# limit_switches.net
KiCad netlist of a schematic drawn in Altium Designer
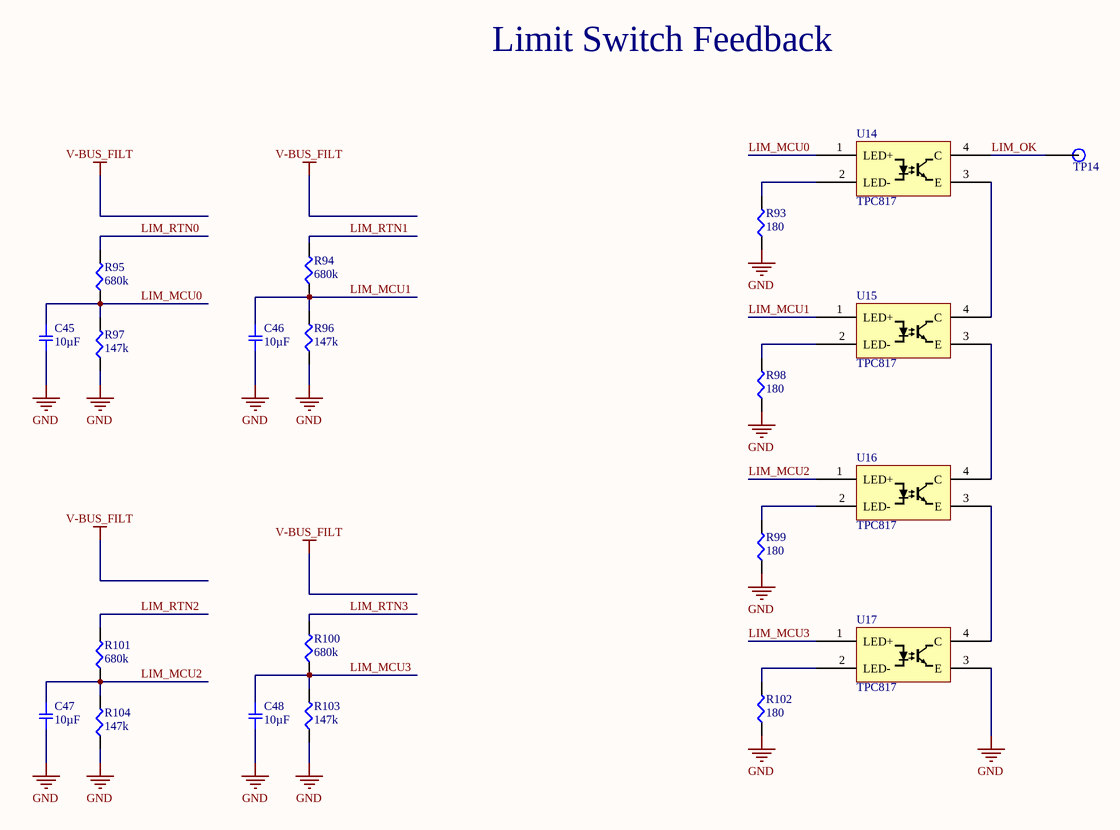
[diagram p0: limit_switches.SchDoc]

(export (version "E")
  (design (tool "Eeschema 10.0.6"))
  (components
    (comp (ref "C45")
      (value "10µF")
      (footprint "SMD-0805C")
      (description "CAP CER 10UF 25V X6S 0805")
      (fields
        (field (name "DIGI-KEY PART NUMBER") "490-10502-1-ND")
        (field (name "PART NUMBER") "GRM21BC81E106KE51L")
      )
      (libsource (lib "capacitor") (part "GRM21BC81E106KE51L"))
    )
    (comp (ref "C46")
      (value "10µF")
      (footprint "SMD-0805C")
      (description "CAP CER 10UF 25V X6S 0805")
      (fields
        (field (name "DIGI-KEY PART NUMBER") "490-10502-1-ND")
        (field (name "PART NUMBER") "GRM21BC81E106KE51L")
      )
      (libsource (lib "capacitor") (part "GRM21BC81E106KE51L"))
    )
    (comp (ref "C47")
      (value "10µF")
      (footprint "SMD-0805C")
      (description "CAP CER 10UF 25V X6S 0805")
      (fields
        (field (name "DIGI-KEY PART NUMBER") "490-10502-1-ND")
        (field (name "PART NUMBER") "GRM21BC81E106KE51L")
      )
      (libsource (lib "capacitor") (part "GRM21BC81E106KE51L"))
    )
    (comp (ref "C48")
      (value "10µF")
      (footprint "SMD-0805C")
      (description "CAP CER 10UF 25V X6S 0805")
      (fields
        (field (name "DIGI-KEY PART NUMBER") "490-10502-1-ND")
        (field (name "PART NUMBER") "GRM21BC81E106KE51L")
      )
      (libsource (lib "capacitor") (part "GRM21BC81E106KE51L"))
    )
    (comp (ref "R93")
      (value "180")
      (footprint "SMD-0805-RES")
      (description "RES SMD 180 OHM 1% 1/8W 0805")
      (fields (field (name "PART NUMBER") "ERJ-6ENF1800V") (field (name "DIGI-KEY PART NUMBER") "P180CCT-ND"))
      (libsource (lib "resistors") (part "ERJ-6ENF1800V"))
    )
    (comp (ref "R94")
      (value "680k")
      (footprint "SMD-0805-RES")
      (description "RES SMD 680K OHM 1% 1/8W 0805")
      (fields
        (field (name "PART NUMBER") "ERJ-6ENF6803V")
        (field (name "DIGI-KEY PART NUMBER") "P680KCCT-ND")
      )
      (libsource (lib "resistors") (part "ERJ-6ENF6803V"))
    )
    (comp (ref "R95")
      (value "680k")
      (footprint "SMD-0805-RES")
      (description "RES SMD 680K OHM 1% 1/8W 0805")
      (fields
        (field (name "PART NUMBER") "ERJ-6ENF6803V")
        (field (name "DIGI-KEY PART NUMBER") "P680KCCT-ND")
      )
      (libsource (lib "resistors") (part "ERJ-6ENF6803V"))
    )
    (comp (ref "R96")
      (value "147k")
      (footprint "SMD-0805-RES")
      (description "RES SMD 147K OHM 1% 1/8W 0805")
      (fields
        (field (name "PART NUMBER") "ERJ-6ENF1473V")
        (field (name "DIGI-KEY PART NUMBER") "P147KCCT-ND")
      )
      (libsource (lib "resistors") (part "ERJ-6ENF1473V"))
    )
    (comp (ref "R97")
      (value "147k")
      (footprint "SMD-0805-RES")
      (description "RES SMD 147K OHM 1% 1/8W 0805")
      (fields
        (field (name "PART NUMBER") "ERJ-6ENF1473V")
        (field (name "DIGI-KEY PART NUMBER") "P147KCCT-ND")
      )
      (libsource (lib "resistors") (part "ERJ-6ENF1473V"))
    )
    (comp (ref "R98")
      (value "180")
      (footprint "SMD-0805-RES")
      (description "RES SMD 180 OHM 1% 1/8W 0805")
      (fields (field (name "PART NUMBER") "ERJ-6ENF1800V") (field (name "DIGI-KEY PART NUMBER") "P180CCT-ND"))
      (libsource (lib "resistors") (part "ERJ-6ENF1800V"))
    )
    (comp (ref "R99")
      (value "180")
      (footprint "SMD-0805-RES")
      (description "RES SMD 180 OHM 1% 1/8W 0805")
      (fields (field (name "PART NUMBER") "ERJ-6ENF1800V") (field (name "DIGI-KEY PART NUMBER") "P180CCT-ND"))
      (libsource (lib "resistors") (part "ERJ-6ENF1800V"))
    )
    (comp (ref "R100")
      (value "680k")
      (footprint "SMD-0805-RES")
      (description "RES SMD 680K OHM 1% 1/8W 0805")
      (fields
        (field (name "PART NUMBER") "ERJ-6ENF6803V")
        (field (name "DIGI-KEY PART NUMBER") "P680KCCT-ND")
      )
      (libsource (lib "resistors") (part "ERJ-6ENF6803V"))
    )
    (comp (ref "R101")
      (value "680k")
      (footprint "SMD-0805-RES")
      (description "RES SMD 680K OHM 1% 1/8W 0805")
      (fields
        (field (name "PART NUMBER") "ERJ-6ENF6803V")
        (field (name "DIGI-KEY PART NUMBER") "P680KCCT-ND")
      )
      (libsource (lib "resistors") (part "ERJ-6ENF6803V"))
    )
    (comp (ref "R102")
      (value "180")
      (footprint "SMD-0805-RES")
      (description "RES SMD 180 OHM 1% 1/8W 0805")
      (fields (field (name "PART NUMBER") "ERJ-6ENF1800V") (field (name "DIGI-KEY PART NUMBER") "P180CCT-ND"))
      (libsource (lib "resistors") (part "ERJ-6ENF1800V"))
    )
    (comp (ref "R103")
      (value "147k")
      (footprint "SMD-0805-RES")
      (description "RES SMD 147K OHM 1% 1/8W 0805")
      (fields
        (field (name "PART NUMBER") "ERJ-6ENF1473V")
        (field (name "DIGI-KEY PART NUMBER") "P147KCCT-ND")
      )
      (libsource (lib "resistors") (part "ERJ-6ENF1473V"))
    )
    (comp (ref "R104")
      (value "147k")
      (footprint "SMD-0805-RES")
      (description "RES SMD 147K OHM 1% 1/8W 0805")
      (fields
        (field (name "PART NUMBER") "ERJ-6ENF1473V")
        (field (name "DIGI-KEY PART NUMBER") "P147KCCT-ND")
      )
      (libsource (lib "resistors") (part "ERJ-6ENF1473V"))
    )
    (comp (ref "TP14")
      (value "TP")
      (footprint "Test Point")
      (description "SMD TEST POINT")
      (libsource (lib "misc") (part "TP"))
    )
    (comp (ref "U14")
      (value "TPC817")
      (footprint "SOT200P1005X328-5N")
      (description "OPTOISO 5KV TRANS 4SOP")
      (fields (field (name "MANUFACTURER") "Taiwan Semi"))
      (libsource (lib "ic") (part "TPC817"))
    )
    (comp (ref "U15")
      (value "TPC817")
      (footprint "SOT200P1005X328-5N")
      (description "OPTOISO 5KV TRANS 4SOP")
      (fields (field (name "MANUFACTURER") "Taiwan Semi"))
      (libsource (lib "ic") (part "TPC817"))
    )
    (comp (ref "U16")
      (value "TPC817")
      (footprint "SOT200P1005X328-5N")
      (description "OPTOISO 5KV TRANS 4SOP")
      (fields (field (name "MANUFACTURER") "Taiwan Semi"))
      (libsource (lib "ic") (part "TPC817"))
    )
    (comp (ref "U17")
      (value "TPC817")
      (footprint "SOT200P1005X328-5N")
      (description "OPTOISO 5KV TRANS 4SOP")
      (fields (field (name "MANUFACTURER") "Taiwan Semi"))
      (libsource (lib "ic") (part "TPC817"))
    )
  )
  (nets
    (net (code "1") (name "/LIM_MCU0") (class "Default")
      (node (ref "C45") (pin "1") (pinfunction "1_1") (pintype "passive"))
      (node (ref "R95") (pin "1") (pinfunction "1_1") (pintype "passive"))
      (node (ref "R97") (pin "2") (pinfunction "2_2") (pintype "passive"))
      (node (ref "U14") (pin "1") (pinfunction "LED+_1") (pintype "passive"))
    )
    (net (code "2") (name "/LIM_MCU1") (class "Default")
      (node (ref "C46") (pin "1") (pinfunction "1_1") (pintype "passive"))
      (node (ref "R94") (pin "1") (pinfunction "1_1") (pintype "passive"))
      (node (ref "R96") (pin "2") (pinfunction "2_2") (pintype "passive"))
      (node (ref "U15") (pin "1") (pinfunction "LED+_1") (pintype "passive"))
    )
    (net (code "3") (name "/LIM_MCU2") (class "Default")
      (node (ref "C47") (pin "1") (pinfunction "1_1") (pintype "passive"))
      (node (ref "R101") (pin "1") (pinfunction "1_1") (pintype "passive"))
      (node (ref "R104") (pin "2") (pinfunction "2_2") (pintype "passive"))
      (node (ref "U16") (pin "1") (pinfunction "LED+_1") (pintype "passive"))
    )
    (net (code "4") (name "/LIM_MCU3") (class "Default")
      (node (ref "C48") (pin "1") (pinfunction "1_1") (pintype "passive"))
      (node (ref "R100") (pin "1") (pinfunction "1_1") (pintype "passive"))
      (node (ref "R103") (pin "2") (pinfunction "2_2") (pintype "passive"))
      (node (ref "U17") (pin "1") (pinfunction "LED+_1") (pintype "passive"))
    )
    (net (code "5") (name "/LIM_OK") (class "Default")
      (node (ref "TP14") (pin "1") (pinfunction "1_1") (pintype "passive"))
      (node (ref "U14") (pin "4") (pinfunction "C_4") (pintype "passive"))
    )
    (net (code "6") (name "/LIM_RTN0") (class "Default")
      (node (ref "R95") (pin "2") (pinfunction "2_2") (pintype "passive"))
    )
    (net (code "7") (name "/LIM_RTN1") (class "Default")
      (node (ref "R94") (pin "2") (pinfunction "2_2") (pintype "passive"))
    )
    (net (code "8") (name "/LIM_RTN2") (class "Default")
      (node (ref "R101") (pin "2") (pinfunction "2_2") (pintype "passive"))
    )
    (net (code "9") (name "/LIM_RTN3") (class "Default")
      (node (ref "R100") (pin "2") (pinfunction "2_2") (pintype "passive"))
    )
    (net (code "10") (name "GND") (class "Default")
      (node (ref "C45") (pin "2") (pinfunction "2_2") (pintype "passive"))
      (node (ref "C46") (pin "2") (pinfunction "2_2") (pintype "passive"))
      (node (ref "C47") (pin "2") (pinfunction "2_2") (pintype "passive"))
      (node (ref "C48") (pin "2") (pinfunction "2_2") (pintype "passive"))
      (node (ref "R102") (pin "1") (pinfunction "1_1") (pintype "passive"))
      (node (ref "R103") (pin "1") (pinfunction "1_1") (pintype "passive"))
      (node (ref "R104") (pin "1") (pinfunction "1_1") (pintype "passive"))
      (node (ref "R93") (pin "1") (pinfunction "1_1") (pintype "passive"))
      (node (ref "R96") (pin "1") (pinfunction "1_1") (pintype "passive"))
      (node (ref "R97") (pin "1") (pinfunction "1_1") (pintype "passive"))
      (node (ref "R98") (pin "1") (pinfunction "1_1") (pintype "passive"))
      (node (ref "R99") (pin "1") (pinfunction "1_1") (pintype "passive"))
      (node (ref "U17") (pin "3") (pinfunction "E_3") (pintype "passive"))
    )
    (net (code "11") (name "Net-(U14-E)") (class "Default")
      (node (ref "U14") (pin "3") (pinfunction "E_3") (pintype "passive"))
      (node (ref "U15") (pin "4") (pinfunction "C_4") (pintype "passive"))
    )
    (net (code "12") (name "Net-(U14-LED-)") (class "Default")
      (node (ref "R93") (pin "2") (pinfunction "2_2") (pintype "passive"))
      (node (ref "U14") (pin "2") (pinfunction "LED-_2") (pintype "passive"))
    )
    (net (code "13") (name "Net-(U15-E)") (class "Default")
      (node (ref "U15") (pin "3") (pinfunction "E_3") (pintype "passive"))
      (node (ref "U16") (pin "4") (pinfunction "C_4") (pintype "passive"))
    )
    (net (code "14") (name "Net-(U15-LED-)") (class "Default")
      (node (ref "R98") (pin "2") (pinfunction "2_2") (pintype "passive"))
      (node (ref "U15") (pin "2") (pinfunction "LED-_2") (pintype "passive"))
    )
    (net (code "15") (name "Net-(U16-E)") (class "Default")
      (node (ref "U16") (pin "3") (pinfunction "E_3") (pintype "passive"))
      (node (ref "U17") (pin "4") (pinfunction "C_4") (pintype "passive"))
    )
    (net (code "16") (name "Net-(U16-LED-)") (class "Default")
      (node (ref "R99") (pin "2") (pinfunction "2_2") (pintype "passive"))
      (node (ref "U16") (pin "2") (pinfunction "LED-_2") (pintype "passive"))
    )
    (net (code "17") (name "Net-(U17-LED-)") (class "Default")
      (node (ref "R102") (pin "2") (pinfunction "2_2") (pintype "passive"))
      (node (ref "U17") (pin "2") (pinfunction "LED-_2") (pintype "passive"))
    )
  )
)
